# CAM-M8Q-Breakout_v11.net
KiCad netlist of a schematic drawn in EAGLE
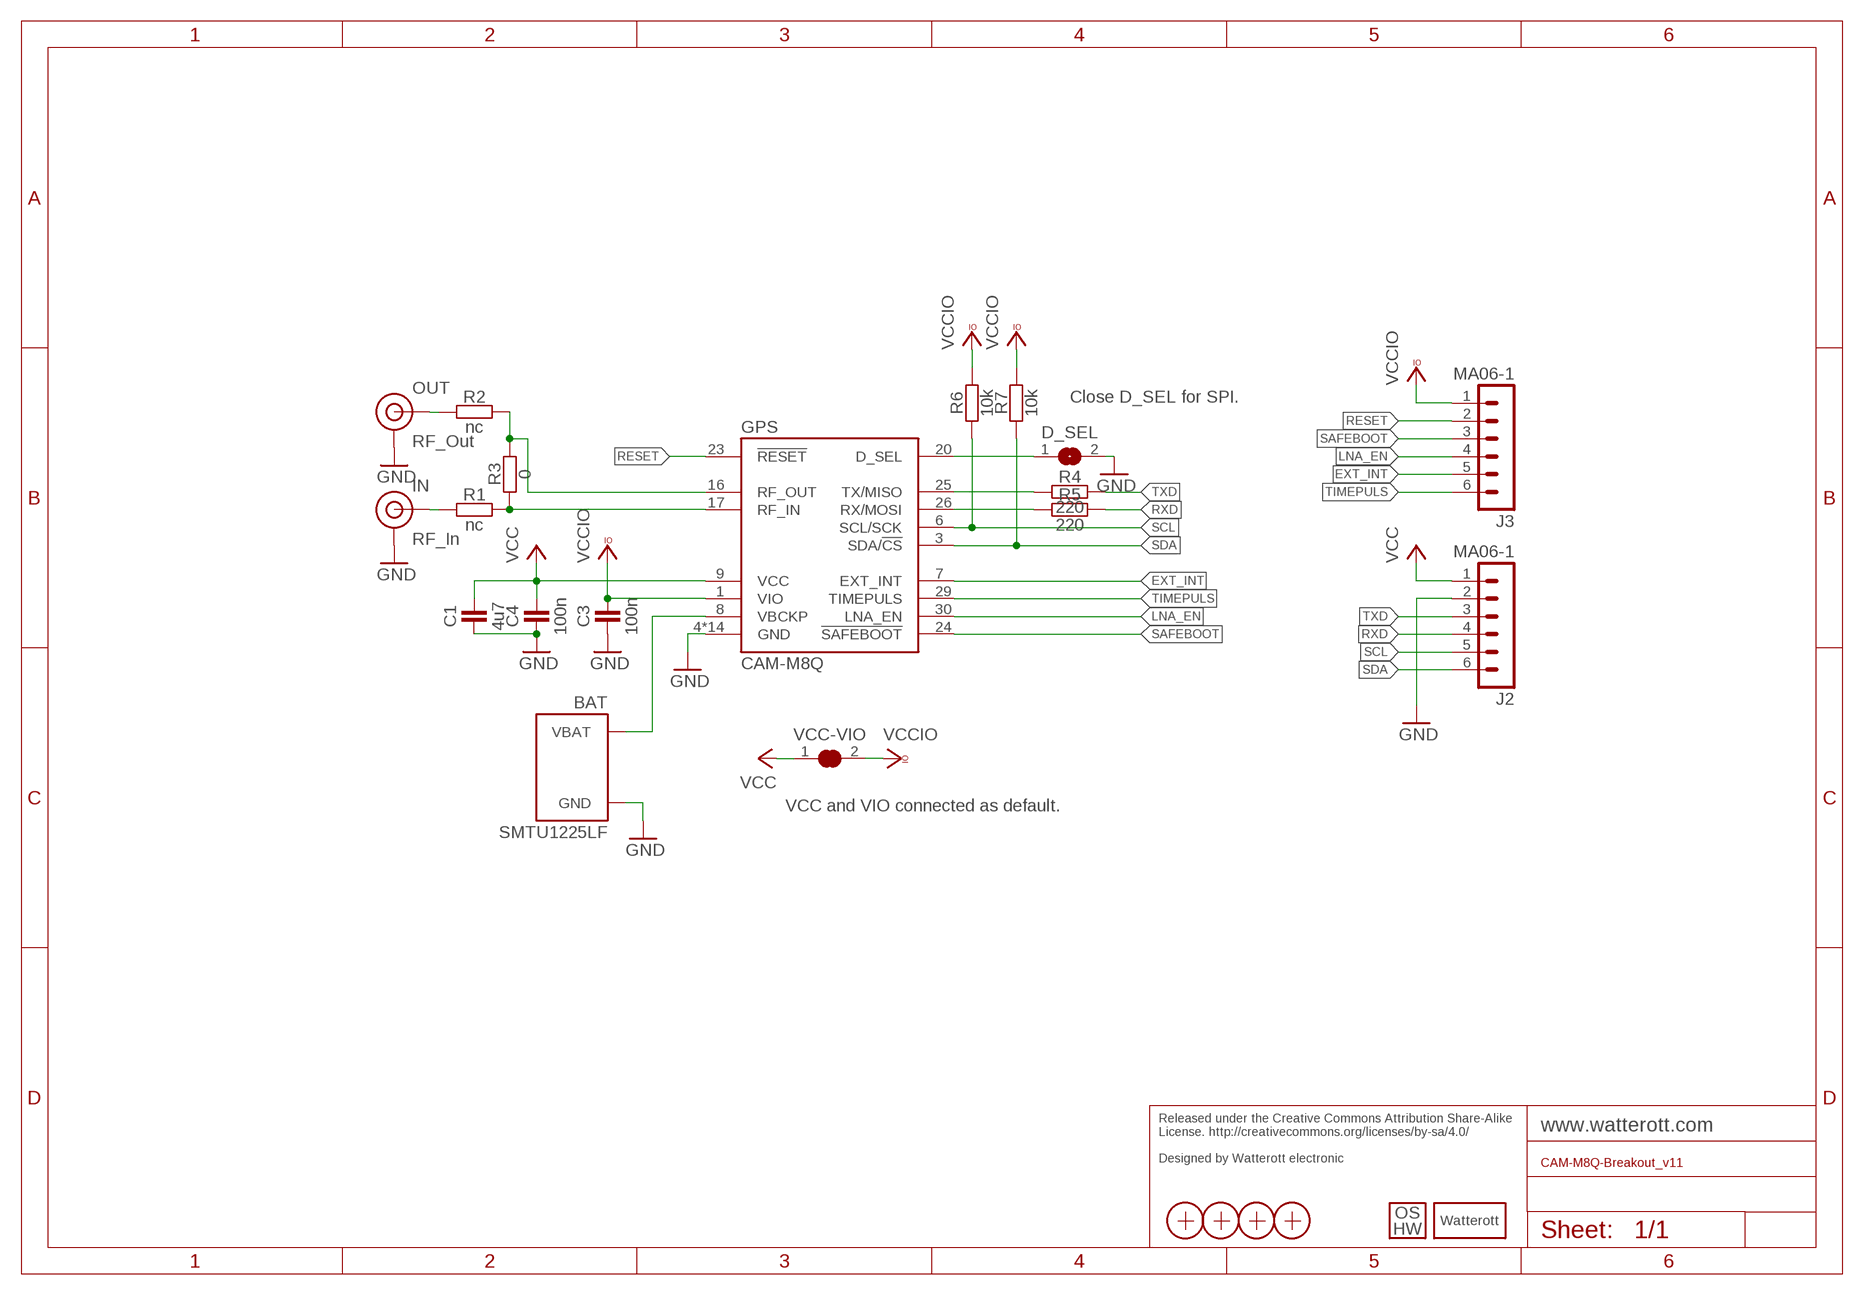
[diagram p0: schematic, sheet 1]

(export (version "E")
  (design (tool "Eeschema 10.0.6"))
  (components
    (comp (ref "BAT")
      (value "SMTU1225LF")
      (footprint "eagle-import:BAT-SMTU1225LF")
      (libsource (lib "eagle-import") (part "BATTERY-SMTU1225LF"))
    )
    (comp (ref "C1")
      (value "4u7")
      (footprint "eagle-import:C0402")
      (libsource (lib "eagle-import") (part "CAPACITOR-0402"))
    )
    (comp (ref "C3")
      (value "100n")
      (footprint "eagle-import:C0402")
      (libsource (lib "eagle-import") (part "CAPACITOR-0402"))
    )
    (comp (ref "C4")
      (value "100n")
      (footprint "eagle-import:C0402")
      (libsource (lib "eagle-import") (part "CAPACITOR-0402"))
    )
    (comp (ref "D_SEL")
      (value "JUMPER2-0603-NC")
      (footprint "eagle-import:JUMPER2-0603_NC")
      (libsource (lib "eagle-import") (part "JUMPER2-0603-NC"))
    )
    (comp (ref "GPS")
      (value "CAM-M8Q")
      (footprint "eagle-import:CAM-M8Q")
      (libsource (lib "eagle-import") (part "CAM-M8Q"))
    )
    (comp (ref "IN")
      (value "RF_In")
      (footprint "eagle-import:U.FL")
      (libsource (lib "eagle-import") (part "U.FL"))
    )
    (comp (ref "J2")
      (value "MA06-1")
      (footprint "eagle-import:MA06-1")
      (libsource (lib "eagle-import") (part "MA06-1"))
    )
    (comp (ref "J3")
      (value "MA06-1")
      (footprint "eagle-import:MA06-1")
      (libsource (lib "eagle-import") (part "MA06-1"))
    )
    (comp (ref "LOGO3")
      (value "LOGO_SPARK-4")
      (footprint "eagle-import:SPARK_4MM")
      (libsource (lib "eagle-import") (part "LOGO_SPARK-4"))
    )
    (comp (ref "LOGO4")
      (value "LOGO_OSHW-2")
      (footprint "eagle-import:OSHW_2MM")
      (libsource (lib "eagle-import") (part "LOGO_OSHW-2"))
    )
    (comp (ref "OUT")
      (value "RF_Out")
      (footprint "eagle-import:U.FL")
      (libsource (lib "eagle-import") (part "U.FL"))
    )
    (comp (ref "R1")
      (value "nc")
      (footprint "eagle-import:C0402")
      (libsource (lib "eagle-import") (part "RESISTOR-0402"))
    )
    (comp (ref "R2")
      (value "nc")
      (footprint "eagle-import:C0402")
      (libsource (lib "eagle-import") (part "RESISTOR-0402"))
    )
    (comp (ref "R3")
      (value "0")
      (footprint "eagle-import:C0402")
      (libsource (lib "eagle-import") (part "RESISTOR-0402"))
    )
    (comp (ref "R4")
      (value "220")
      (footprint "eagle-import:C0402")
      (libsource (lib "eagle-import") (part "RESISTOR-0402"))
    )
    (comp (ref "R5")
      (value "220")
      (footprint "eagle-import:C0402")
      (libsource (lib "eagle-import") (part "RESISTOR-0402"))
    )
    (comp (ref "R6")
      (value "10k")
      (footprint "eagle-import:C0402")
      (libsource (lib "eagle-import") (part "RESISTOR-0402"))
    )
    (comp (ref "R7")
      (value "10k")
      (footprint "eagle-import:C0402")
      (libsource (lib "eagle-import") (part "RESISTOR-0402"))
    )
    (comp (ref "VCC-VIO")
      (value "JUMPER2-0603-NC")
      (footprint "eagle-import:JUMPER2-0603_NC")
      (libsource (lib "eagle-import") (part "JUMPER2-0603-NC"))
    )
    (comp (ref "X1")
      (value "PASSER-07")
      (footprint "eagle-import:PASSER_07MM")
      (libsource (lib "eagle-import") (part "PASSER-07"))
    )
    (comp (ref "X2")
      (value "PASSER-07")
      (footprint "eagle-import:PASSER_07MM")
      (libsource (lib "eagle-import") (part "PASSER-07"))
    )
    (comp (ref "X3")
      (value "PASSER-07")
      (footprint "eagle-import:PASSER_07MM")
      (libsource (lib "eagle-import") (part "PASSER-07"))
    )
    (comp (ref "X4")
      (value "PASSER-07")
      (footprint "eagle-import:PASSER_07MM")
      (libsource (lib "eagle-import") (part "PASSER-07"))
    )
  )
  (nets
    (net (code "1") (name "EXT_INT") (class "Default")
      (node (ref "GPS") (pin "7") (pinfunction "EXT_INT_7") (pintype "bidirectional"))
      (node (ref "J3") (pin "5") (pinfunction "5_5") (pintype "passive"))
    )
    (net (code "2") (name "GND") (class "Default")
      (node (ref "BAT") (pin "-") (pinfunction "GND_-") (pintype "power_in"))
      (node (ref "C1") (pin "1") (pinfunction "1_1") (pintype "passive"))
      (node (ref "C3") (pin "1") (pinfunction "1_1") (pintype "passive"))
      (node (ref "C4") (pin "1") (pinfunction "1_1") (pintype "passive"))
      (node (ref "D_SEL") (pin "2") (pinfunction "2_2") (pintype "passive"))
      (node (ref "GPS") (pin "10") (pinfunction "GND_10") (pintype "power_in"))
      (node (ref "GPS") (pin "11") (pinfunction "GND_11") (pintype "power_in"))
      (node (ref "GPS") (pin "12") (pinfunction "GND_12") (pintype "power_in"))
      (node (ref "GPS") (pin "13") (pinfunction "GND_13") (pintype "power_in"))
      (node (ref "GPS") (pin "14") (pinfunction "GND_14") (pintype "power_in"))
      (node (ref "GPS") (pin "15") (pinfunction "GND_15") (pintype "power_in"))
      (node (ref "GPS") (pin "18") (pinfunction "GND_18") (pintype "power_in"))
      (node (ref "GPS") (pin "19") (pinfunction "GND_19") (pintype "power_in"))
      (node (ref "GPS") (pin "21") (pinfunction "GND_21") (pintype "power_in"))
      (node (ref "GPS") (pin "22") (pinfunction "GND_22") (pintype "power_in"))
      (node (ref "GPS") (pin "27") (pinfunction "GND_27") (pintype "power_in"))
      (node (ref "GPS") (pin "31") (pinfunction "GND_31") (pintype "power_in"))
      (node (ref "GPS") (pin "4") (pinfunction "GND_4") (pintype "power_in"))
      (node (ref "GPS") (pin "5") (pinfunction "GND_5") (pintype "power_in"))
      (node (ref "IN") (pin "1") (pinfunction "GND_1") (pintype "bidirectional"))
      (node (ref "IN") (pin "2") (pinfunction "GND_2") (pintype "bidirectional"))
      (node (ref "J2") (pin "2") (pinfunction "2_2") (pintype "passive"))
      (node (ref "OUT") (pin "1") (pinfunction "GND_1") (pintype "bidirectional"))
      (node (ref "OUT") (pin "2") (pinfunction "GND_2") (pintype "bidirectional"))
    )
    (net (code "3") (name "LNA_EN") (class "Default")
      (node (ref "GPS") (pin "30") (pinfunction "LNA_EN_30") (pintype "bidirectional"))
      (node (ref "J3") (pin "4") (pinfunction "4_4") (pintype "passive"))
    )
    (net (code "4") (name "Net-(BAT-VBAT)") (class "Default")
      (node (ref "BAT") (pin "+") (pinfunction "VBAT_+") (pintype "power_in"))
      (node (ref "GPS") (pin "8") (pinfunction "VBCKP_8") (pintype "power_in"))
    )
    (net (code "5") (name "Net-(GPS-D_SEL)") (class "Default")
      (node (ref "D_SEL") (pin "1") (pinfunction "1_1") (pintype "passive"))
      (node (ref "GPS") (pin "20") (pinfunction "D_SEL_20") (pintype "bidirectional"))
    )
    (net (code "6") (name "Net-(GPS-RF_IN)") (class "Default")
      (node (ref "GPS") (pin "17") (pinfunction "RF_IN_17") (pintype "input"))
      (node (ref "R1") (pin "2") (pinfunction "2_2") (pintype "passive"))
      (node (ref "R3") (pin "1") (pinfunction "1_1") (pintype "passive"))
    )
    (net (code "7") (name "Net-(GPS-RF_OUT)") (class "Default")
      (node (ref "GPS") (pin "16") (pinfunction "RF_OUT_16") (pintype "output"))
      (node (ref "R2") (pin "2") (pinfunction "2_2") (pintype "passive"))
      (node (ref "R3") (pin "2") (pinfunction "2_2") (pintype "passive"))
    )
    (net (code "8") (name "Net-(GPS-RX{slash}MOSI)") (class "Default")
      (node (ref "GPS") (pin "26") (pinfunction "RX/MOSI_26") (pintype "input"))
      (node (ref "R5") (pin "1") (pinfunction "1_1") (pintype "passive"))
    )
    (net (code "9") (name "Net-(GPS-TX{slash}MISO)") (class "Default")
      (node (ref "GPS") (pin "25") (pinfunction "TX/MISO_25") (pintype "output"))
      (node (ref "R4") (pin "1") (pinfunction "1_1") (pintype "passive"))
    )
    (net (code "10") (name "Net-(IN-SIGNAL)") (class "Default")
      (node (ref "IN") (pin "FEED") (pinfunction "SIGNAL_FEED") (pintype "bidirectional"))
      (node (ref "R1") (pin "1") (pinfunction "1_1") (pintype "passive"))
    )
    (net (code "11") (name "Net-(OUT-SIGNAL)") (class "Default")
      (node (ref "OUT") (pin "FEED") (pinfunction "SIGNAL_FEED") (pintype "bidirectional"))
      (node (ref "R2") (pin "1") (pinfunction "1_1") (pintype "passive"))
    )
    (net (code "12") (name "RESET") (class "Default")
      (node (ref "GPS") (pin "23") (pinfunction "~{RESET}_23") (pintype "input"))
      (node (ref "J3") (pin "2") (pinfunction "2_2") (pintype "passive"))
    )
    (net (code "13") (name "RXD") (class "Default")
      (node (ref "J2") (pin "4") (pinfunction "4_4") (pintype "passive"))
      (node (ref "R5") (pin "2") (pinfunction "2_2") (pintype "passive"))
    )
    (net (code "14") (name "SAFEBOOT") (class "Default")
      (node (ref "GPS") (pin "24") (pinfunction "~{SAFEBOOT}_24") (pintype "bidirectional"))
      (node (ref "J3") (pin "3") (pinfunction "3_3") (pintype "passive"))
    )
    (net (code "15") (name "SCL") (class "Default")
      (node (ref "GPS") (pin "6") (pinfunction "SCL/SCK_6") (pintype "bidirectional"))
      (node (ref "J2") (pin "5") (pinfunction "5_5") (pintype "passive"))
      (node (ref "R6") (pin "1") (pinfunction "1_1") (pintype "passive"))
    )
    (net (code "16") (name "SDA") (class "Default")
      (node (ref "GPS") (pin "3") (pinfunction "SDA/~{CS}_3") (pintype "bidirectional"))
      (node (ref "J2") (pin "6") (pinfunction "6_6") (pintype "passive"))
      (node (ref "R7") (pin "1") (pinfunction "1_1") (pintype "passive"))
    )
    (net (code "17") (name "TIMEPULS") (class "Default")
      (node (ref "GPS") (pin "29") (pinfunction "TIMEPULS_29") (pintype "output"))
      (node (ref "J3") (pin "6") (pinfunction "6_6") (pintype "passive"))
    )
    (net (code "18") (name "TXD") (class "Default")
      (node (ref "J2") (pin "3") (pinfunction "3_3") (pintype "passive"))
      (node (ref "R4") (pin "2") (pinfunction "2_2") (pintype "passive"))
    )
    (net (code "19") (name "VCC") (class "Default")
      (node (ref "C1") (pin "2") (pinfunction "2_2") (pintype "passive"))
      (node (ref "C4") (pin "2") (pinfunction "2_2") (pintype "passive"))
      (node (ref "GPS") (pin "9") (pinfunction "VCC_9") (pintype "power_in"))
      (node (ref "J2") (pin "1") (pinfunction "1_1") (pintype "passive"))
      (node (ref "VCC-VIO") (pin "1") (pinfunction "1_1") (pintype "passive"))
    )
    (net (code "20") (name "VCCIO") (class "Default")
      (node (ref "C3") (pin "2") (pinfunction "2_2") (pintype "passive"))
      (node (ref "GPS") (pin "1") (pinfunction "VIO_1") (pintype "power_in"))
      (node (ref "J3") (pin "1") (pinfunction "1_1") (pintype "passive"))
      (node (ref "R6") (pin "2") (pinfunction "2_2") (pintype "passive"))
      (node (ref "R7") (pin "2") (pinfunction "2_2") (pintype "passive"))
      (node (ref "VCC-VIO") (pin "2") (pinfunction "2_2") (pintype "passive"))
    )
  )
)
